# DressCode.net
KiCad netlist of a schematic drawn in EAGLE
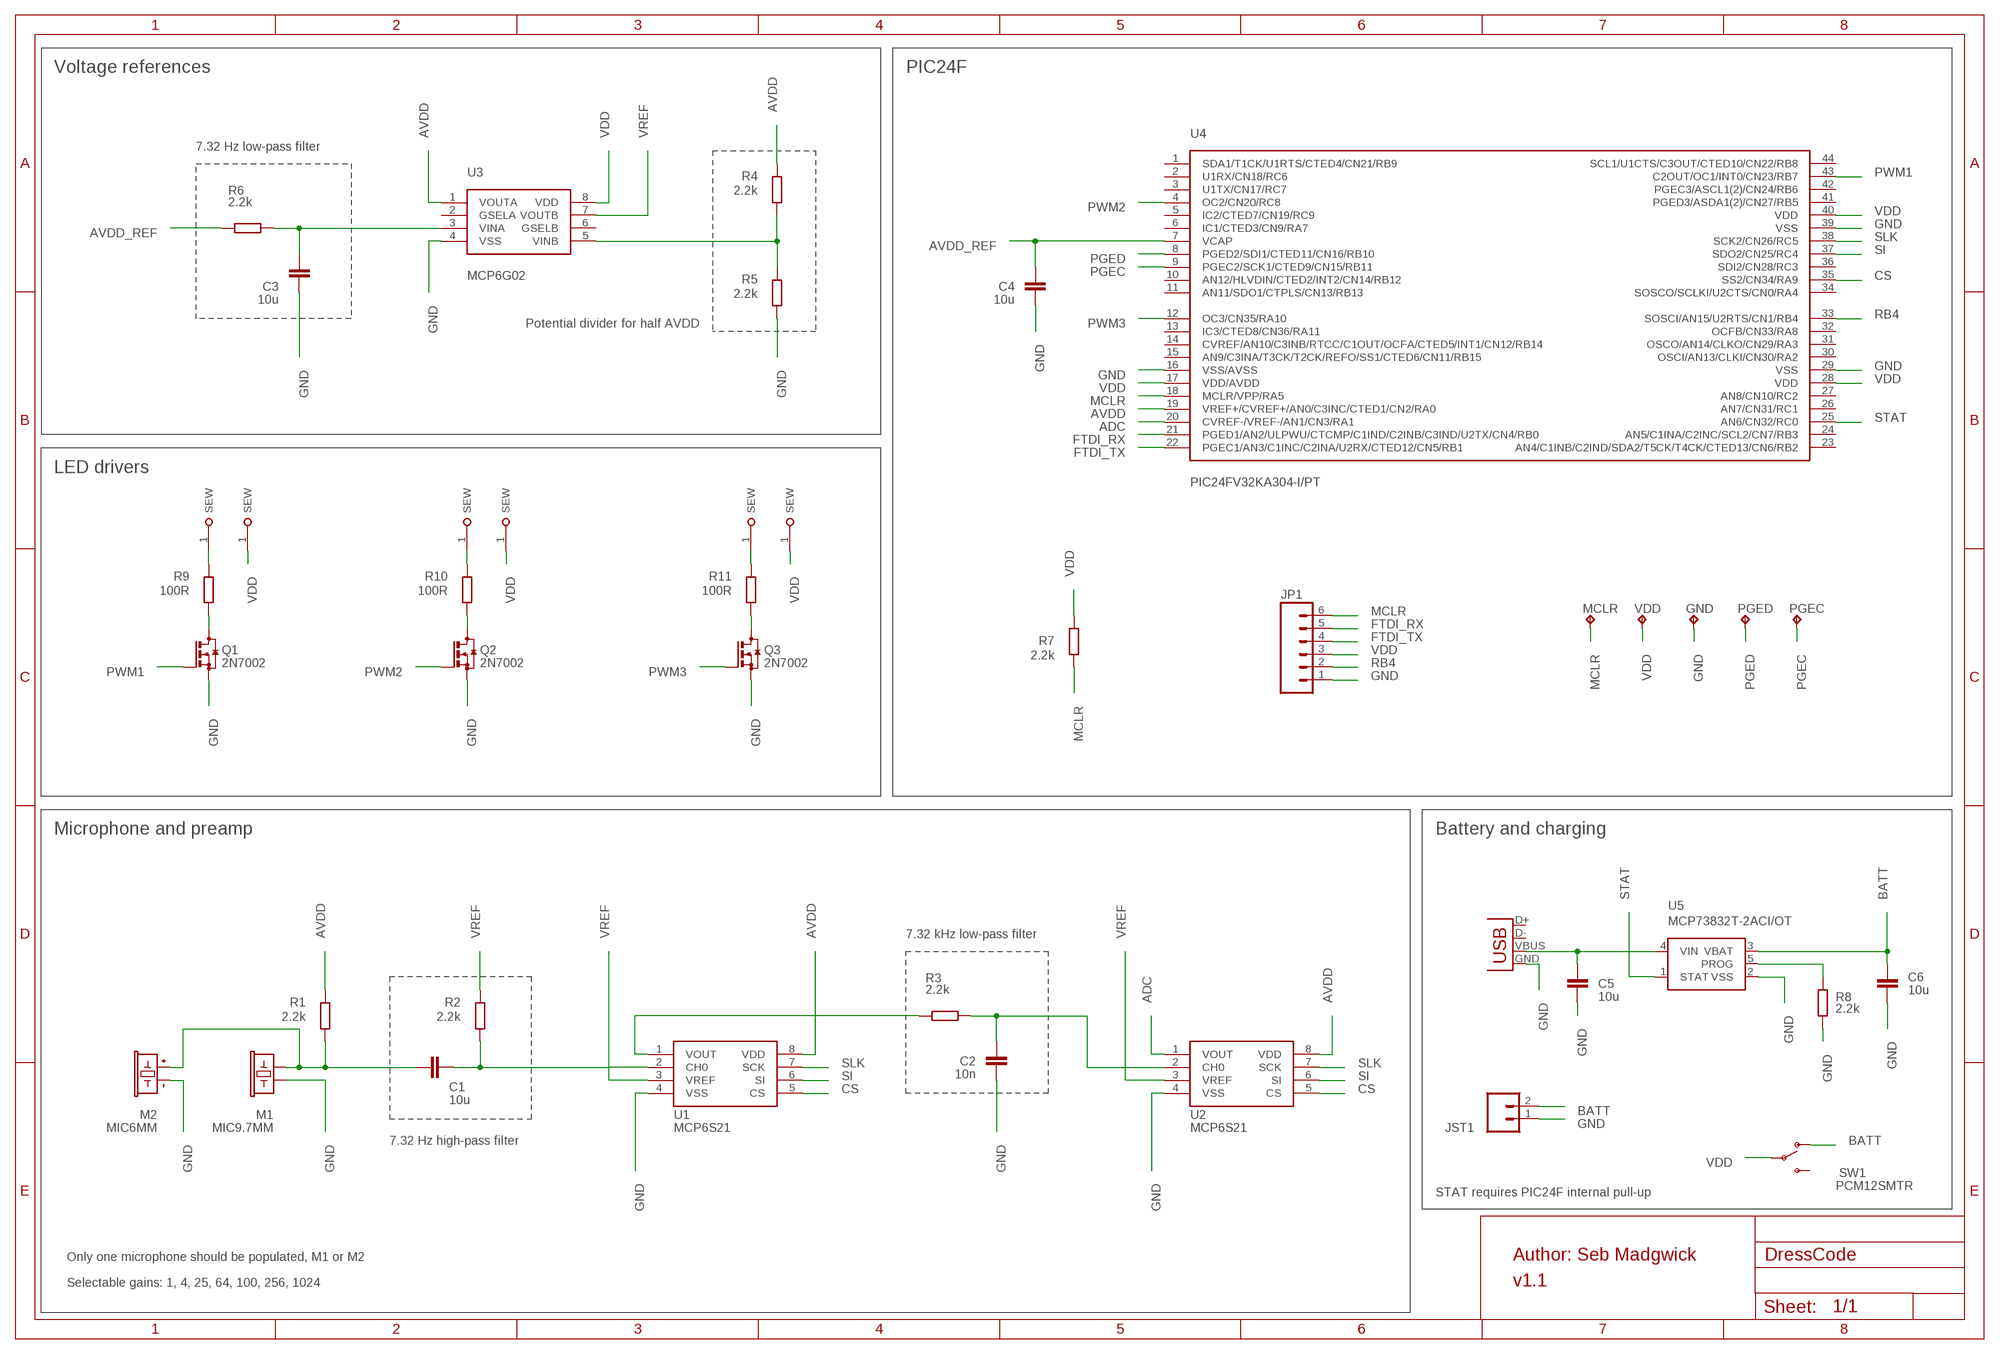
[diagram p0: schematic, sheet 1]

(export (version "E")
  (design (tool "Eeschema 10.0.6"))
  (components
    (comp (ref "C1")
      (value "10u")
      (footprint "eagle-import:C0805")
      (libsource (lib "eagle-import") (part "C-EUC0805"))
    )
    (comp (ref "C2")
      (value "10n")
      (footprint "eagle-import:C0805")
      (libsource (lib "eagle-import") (part "C-EUC0805"))
    )
    (comp (ref "C3")
      (value "10u")
      (footprint "eagle-import:C0805")
      (libsource (lib "eagle-import") (part "C-EUC0805"))
    )
    (comp (ref "C4")
      (value "10u")
      (footprint "eagle-import:C0805")
      (libsource (lib "eagle-import") (part "C-EUC0805"))
    )
    (comp (ref "C5")
      (value "10u")
      (footprint "eagle-import:C0805")
      (libsource (lib "eagle-import") (part "C-EUC0805"))
    )
    (comp (ref "C6")
      (value "10u")
      (footprint "eagle-import:C0805")
      (libsource (lib "eagle-import") (part "C-EUC0805"))
    )
    (comp (ref "GND")
      (value "TPTP16R")
      (footprint "eagle-import:TP16R")
      (libsource (lib "eagle-import") (part "TPTP16R"))
    )
    (comp (ref "JP1")
      (value "M06SIP")
      (footprint "eagle-import:1X06")
      (libsource (lib "eagle-import") (part "M06SIP"))
    )
    (comp (ref "JST1")
      (value "M02-JST-2MM-SMT")
      (footprint "eagle-import:JST-2-SMD")
      (libsource (lib "eagle-import") (part "M02-JST-2MM-SMT"))
    )
    (comp (ref "M1")
      (value "MIC9.7MM")
      (footprint "eagle-import:MIC-9.7MM")
      (libsource (lib "eagle-import") (part "MIC9.7MM"))
    )
    (comp (ref "M2")
      (value "MIC6MM")
      (footprint "eagle-import:MIC-SMD")
      (libsource (lib "eagle-import") (part "MIC6MM"))
    )
    (comp (ref "MCLR")
      (value "TPTP16R")
      (footprint "eagle-import:TP16R")
      (libsource (lib "eagle-import") (part "TPTP16R"))
    )
    (comp (ref "PGEC")
      (value "TPTP16R")
      (footprint "eagle-import:TP16R")
      (libsource (lib "eagle-import") (part "TPTP16R"))
    )
    (comp (ref "PGED")
      (value "TPTP16R")
      (footprint "eagle-import:TP16R")
      (libsource (lib "eagle-import") (part "TPTP16R"))
    )
    (comp (ref "Q1")
      (value "2N7002")
      (footprint "eagle-import:SOT23")
      (libsource (lib "eagle-import") (part "BSS123"))
    )
    (comp (ref "Q2")
      (value "2N7002")
      (footprint "eagle-import:SOT23")
      (libsource (lib "eagle-import") (part "BSS123"))
    )
    (comp (ref "Q3")
      (value "2N7002")
      (footprint "eagle-import:SOT23")
      (libsource (lib "eagle-import") (part "BSS123"))
    )
    (comp (ref "R1")
      (value "2.2k")
      (footprint "eagle-import:R0805")
      (libsource (lib "eagle-import") (part "R-EU_R0805"))
    )
    (comp (ref "R2")
      (value "2.2k")
      (footprint "eagle-import:R0805")
      (libsource (lib "eagle-import") (part "R-EU_R0805"))
    )
    (comp (ref "R3")
      (value "2.2k")
      (footprint "eagle-import:R0805")
      (libsource (lib "eagle-import") (part "R-EU_R0805"))
    )
    (comp (ref "R4")
      (value "2.2k")
      (footprint "eagle-import:R0805")
      (libsource (lib "eagle-import") (part "R-EU_R0805"))
    )
    (comp (ref "R5")
      (value "2.2k")
      (footprint "eagle-import:R0805")
      (libsource (lib "eagle-import") (part "R-EU_R0805"))
    )
    (comp (ref "R6")
      (value "2.2k")
      (footprint "eagle-import:R0805")
      (libsource (lib "eagle-import") (part "R-EU_R0805"))
    )
    (comp (ref "R7")
      (value "2.2k")
      (footprint "eagle-import:R0805")
      (libsource (lib "eagle-import") (part "R-EU_R0805"))
    )
    (comp (ref "R8")
      (value "2.2k")
      (footprint "eagle-import:R0805")
      (libsource (lib "eagle-import") (part "R-EU_R0805"))
    )
    (comp (ref "R9")
      (value "100R")
      (footprint "eagle-import:R0805")
      (libsource (lib "eagle-import") (part "R-EU_R0805"))
    )
    (comp (ref "R10")
      (value "100R")
      (footprint "eagle-import:R0805")
      (libsource (lib "eagle-import") (part "R-EU_R0805"))
    )
    (comp (ref "R11")
      (value "100R")
      (footprint "eagle-import:R0805")
      (libsource (lib "eagle-import") (part "R-EU_R0805"))
    )
    (comp (ref "SW1")
      (value "PCM12SMTR")
      (footprint "eagle-import:PCM12SMTR")
      (libsource (lib "eagle-import") (part "PCM12SMTR"))
    )
    (comp (ref "U$4")
      (value "DRESSCODE_SEW_PADC")
      (footprint "eagle-import:DRESSCODE_SEW_PAD_CIRC")
      (libsource (lib "eagle-import") (part "DRESSCODE_SEW_PADC"))
    )
    (comp (ref "U$5")
      (value "DRESSCODE_SEW_PADC")
      (footprint "eagle-import:DRESSCODE_SEW_PAD_CIRC")
      (libsource (lib "eagle-import") (part "DRESSCODE_SEW_PADC"))
    )
    (comp (ref "U$6")
      (value "DRESSCODE_SEW_PADC")
      (footprint "eagle-import:DRESSCODE_SEW_PAD_CIRC")
      (libsource (lib "eagle-import") (part "DRESSCODE_SEW_PADC"))
    )
    (comp (ref "U$7")
      (value "DRESSCODE_SEW_PADS")
      (footprint "eagle-import:DRESSCODE_SEW_PAD_SQR")
      (libsource (lib "eagle-import") (part "DRESSCODE_SEW_PADS"))
    )
    (comp (ref "U$8")
      (value "DRESSCODE_SEW_PADS")
      (footprint "eagle-import:DRESSCODE_SEW_PAD_SQR")
      (libsource (lib "eagle-import") (part "DRESSCODE_SEW_PADS"))
    )
    (comp (ref "U$10")
      (value "DRESSCODE_SEW_PADS")
      (footprint "eagle-import:DRESSCODE_SEW_PAD_SQR")
      (libsource (lib "eagle-import") (part "DRESSCODE_SEW_PADS"))
    )
    (comp (ref "U1")
      (value "MCP6S21")
      (footprint "eagle-import:SOIC-8")
      (libsource (lib "eagle-import") (part "MCP6S21"))
    )
    (comp (ref "U2")
      (value "MCP6S21")
      (footprint "eagle-import:SOIC-8")
      (libsource (lib "eagle-import") (part "MCP6S21"))
    )
    (comp (ref "U3")
      (value "MCP6G02")
      (footprint "eagle-import:SOIC-8")
      (libsource (lib "eagle-import") (part "MCP6G02"))
    )
    (comp (ref "U4")
      (value "PIC24FV32KA304-I/PT")
      (footprint "eagle-import:TQFP44")
      (libsource (lib "eagle-import") (part "PIC24FV32KA304-I/PT"))
    )
    (comp (ref "U5")
      (value "MCP73832T-2ACI/OT")
      (footprint "eagle-import:SOT23-5")
      (libsource (lib "eagle-import") (part "MCP73831"))
    )
    (comp (ref "USB1")
      (value "USB-MICROB")
      (footprint "eagle-import:USB-MICROB")
      (libsource (lib "eagle-import") (part "USB-MICROB"))
    )
    (comp (ref "VDD")
      (value "TPTP16R")
      (footprint "eagle-import:TP16R")
      (libsource (lib "eagle-import") (part "TPTP16R"))
    )
  )
  (nets
    (net (code "1") (name "/ADC") (class "Default")
      (node (ref "U2") (pin "1") (pinfunction "VOUT_1") (pintype "bidirectional"))
      (node (ref "U4") (pin "20") (pinfunction "CVREF-/VREF-/AN1/CN3/RA1_20") (pintype "bidirectional"))
    )
    (net (code "2") (name "/AVDD") (class "Default")
      (node (ref "R1") (pin "2") (pinfunction "2_2") (pintype "passive"))
      (node (ref "R4") (pin "2") (pinfunction "2_2") (pintype "passive"))
      (node (ref "U1") (pin "8") (pinfunction "VDD_8") (pintype "bidirectional"))
      (node (ref "U2") (pin "8") (pinfunction "VDD_8") (pintype "bidirectional"))
      (node (ref "U3") (pin "1") (pinfunction "VOUTA_1") (pintype "bidirectional"))
      (node (ref "U4") (pin "19") (pinfunction "VREF+/CVREF+/AN0/C3INC/CTED1/CN2/RA0_19") (pintype "bidirectional"))
    )
    (net (code "3") (name "/AVDD_REF") (class "Default")
      (node (ref "C4") (pin "2") (pinfunction "2_2") (pintype "passive"))
      (node (ref "R6") (pin "1") (pinfunction "1_1") (pintype "passive"))
      (node (ref "U4") (pin "7") (pinfunction "VCAP_7") (pintype "bidirectional"))
    )
    (net (code "4") (name "/BATT") (class "Default")
      (node (ref "C6") (pin "2") (pinfunction "2_2") (pintype "passive"))
      (node (ref "JST1") (pin "2") (pinfunction "2_2") (pintype "passive"))
      (node (ref "SW1") (pin "1") (pinfunction "O_1") (pintype "passive"))
      (node (ref "U5") (pin "3") (pinfunction "VBAT_3") (pintype "power_in"))
    )
    (net (code "5") (name "/CS") (class "Default")
      (node (ref "U1") (pin "5") (pinfunction "CS_5") (pintype "bidirectional"))
      (node (ref "U2") (pin "5") (pinfunction "CS_5") (pintype "bidirectional"))
      (node (ref "U4") (pin "35") (pinfunction "SS2/CN34/RA9_35") (pintype "bidirectional"))
    )
    (net (code "6") (name "/FTDI_RX") (class "Default")
      (node (ref "JP1") (pin "5") (pinfunction "5_5") (pintype "passive"))
      (node (ref "U4") (pin "21") (pinfunction "PGED1/AN2/ULPWU/CTCMP/C1IND/C2INB/C3IND/U2TX/CN4/RB0_21") (pintype "bidirectional"))
    )
    (net (code "7") (name "/FTDI_TX") (class "Default")
      (node (ref "JP1") (pin "4") (pinfunction "4_4") (pintype "passive"))
      (node (ref "U4") (pin "22") (pinfunction "PGEC1/AN3/C1INC/C2INA/U2RX/CTED12/CN5/RB1_22") (pintype "bidirectional"))
    )
    (net (code "8") (name "/GND") (class "Default")
      (node (ref "C2") (pin "2") (pinfunction "2_2") (pintype "passive"))
      (node (ref "C3") (pin "1") (pinfunction "1_1") (pintype "passive"))
      (node (ref "C4") (pin "1") (pinfunction "1_1") (pintype "passive"))
      (node (ref "C5") (pin "1") (pinfunction "1_1") (pintype "passive"))
      (node (ref "C6") (pin "1") (pinfunction "1_1") (pintype "passive"))
      (node (ref "GND") (pin "TP") (pinfunction "TP_TP") (pintype "input"))
      (node (ref "JP1") (pin "1") (pinfunction "1_1") (pintype "passive"))
      (node (ref "JST1") (pin "1") (pinfunction "1_1") (pintype "passive"))
      (node (ref "M1") (pin "2") (pinfunction "2_2") (pintype "passive"))
      (node (ref "M2") (pin "-") (pinfunction "-_-") (pintype "passive"))
      (node (ref "Q1") (pin "2") (pinfunction "S_2") (pintype "passive"))
      (node (ref "Q2") (pin "2") (pinfunction "S_2") (pintype "passive"))
      (node (ref "Q3") (pin "2") (pinfunction "S_2") (pintype "passive"))
      (node (ref "R5") (pin "1") (pinfunction "1_1") (pintype "passive"))
      (node (ref "R8") (pin "1") (pinfunction "1_1") (pintype "passive"))
      (node (ref "U1") (pin "4") (pinfunction "VSS_4") (pintype "bidirectional"))
      (node (ref "U2") (pin "4") (pinfunction "VSS_4") (pintype "bidirectional"))
      (node (ref "U3") (pin "4") (pinfunction "VSS_4") (pintype "bidirectional"))
      (node (ref "U4") (pin "16") (pinfunction "VSS/AVSS_16") (pintype "bidirectional"))
      (node (ref "U4") (pin "29") (pinfunction "VSS_29") (pintype "bidirectional"))
      (node (ref "U4") (pin "39") (pinfunction "VSS_39") (pintype "bidirectional"))
      (node (ref "U5") (pin "2") (pinfunction "VSS_2") (pintype "power_in"))
      (node (ref "USB1") (pin "GND") (pinfunction "GND_GND") (pintype "bidirectional"))
    )
    (net (code "9") (name "/MCLR") (class "Default")
      (node (ref "JP1") (pin "6") (pinfunction "6_6") (pintype "passive"))
      (node (ref "MCLR") (pin "TP") (pinfunction "TP_TP") (pintype "input"))
      (node (ref "R7") (pin "1") (pinfunction "1_1") (pintype "passive"))
      (node (ref "U4") (pin "18") (pinfunction "MCLR/VPP/RA5_18") (pintype "bidirectional"))
    )
    (net (code "10") (name "/PGEC") (class "Default")
      (node (ref "PGEC") (pin "TP") (pinfunction "TP_TP") (pintype "input"))
      (node (ref "U4") (pin "9") (pinfunction "PGEC2/SCK1/CTED9/CN15/RB11_9") (pintype "bidirectional"))
    )
    (net (code "11") (name "/PGED") (class "Default")
      (node (ref "PGED") (pin "TP") (pinfunction "TP_TP") (pintype "input"))
      (node (ref "U4") (pin "8") (pinfunction "PGED2/SDI1/CTED11/CN16/RB10_8") (pintype "bidirectional"))
    )
    (net (code "12") (name "/PWM1") (class "Default")
      (node (ref "Q1") (pin "1") (pinfunction "G_1") (pintype "passive"))
      (node (ref "U4") (pin "43") (pinfunction "C2OUT/OC1/INT0/CN23/RB7_43") (pintype "bidirectional"))
    )
    (net (code "13") (name "/PWM2") (class "Default")
      (node (ref "Q2") (pin "1") (pinfunction "G_1") (pintype "passive"))
      (node (ref "U4") (pin "4") (pinfunction "OC2/CN20/RC8_4") (pintype "bidirectional"))
    )
    (net (code "14") (name "/PWM3") (class "Default")
      (node (ref "Q3") (pin "1") (pinfunction "G_1") (pintype "passive"))
      (node (ref "U4") (pin "12") (pinfunction "OC3/CN35/RA10_12") (pintype "bidirectional"))
    )
    (net (code "15") (name "/RB4") (class "Default")
      (node (ref "JP1") (pin "2") (pinfunction "2_2") (pintype "passive"))
      (node (ref "U4") (pin "33") (pinfunction "SOSCI/AN15/U2RTS/CN1/RB4_33") (pintype "bidirectional"))
    )
    (net (code "16") (name "/SI") (class "Default")
      (node (ref "U1") (pin "6") (pinfunction "SI_6") (pintype "bidirectional"))
      (node (ref "U2") (pin "6") (pinfunction "SI_6") (pintype "bidirectional"))
      (node (ref "U4") (pin "37") (pinfunction "SDO2/CN25/RC4_37") (pintype "bidirectional"))
    )
    (net (code "17") (name "/SLK") (class "Default")
      (node (ref "U1") (pin "7") (pinfunction "SCK_7") (pintype "bidirectional"))
      (node (ref "U2") (pin "7") (pinfunction "SCK_7") (pintype "bidirectional"))
      (node (ref "U4") (pin "38") (pinfunction "SCK2/CN26/RC5_38") (pintype "bidirectional"))
    )
    (net (code "18") (name "/STAT") (class "Default")
      (node (ref "U4") (pin "25") (pinfunction "AN6/CN32/RC0_25") (pintype "bidirectional"))
      (node (ref "U5") (pin "1") (pinfunction "STAT_1") (pintype "output"))
    )
    (net (code "19") (name "/VDD") (class "Default")
      (node (ref "JP1") (pin "3") (pinfunction "3_3") (pintype "passive"))
      (node (ref "R7") (pin "2") (pinfunction "2_2") (pintype "passive"))
      (node (ref "SW1") (pin "2") (pinfunction "P_2") (pintype "passive"))
      (node (ref "U$4") (pin "1") (pinfunction "SEW_1") (pintype "bidirectional"))
      (node (ref "U$5") (pin "1") (pinfunction "SEW_1") (pintype "bidirectional"))
      (node (ref "U$6") (pin "1") (pinfunction "SEW_1") (pintype "bidirectional"))
      (node (ref "U3") (pin "8") (pinfunction "VDD_8") (pintype "bidirectional"))
      (node (ref "U4") (pin "17") (pinfunction "VDD/AVDD_17") (pintype "bidirectional"))
      (node (ref "U4") (pin "28") (pinfunction "VDD_28") (pintype "bidirectional"))
      (node (ref "U4") (pin "40") (pinfunction "VDD_40") (pintype "bidirectional"))
      (node (ref "VDD") (pin "TP") (pinfunction "TP_TP") (pintype "input"))
    )
    (net (code "20") (name "/VREF") (class "Default")
      (node (ref "R2") (pin "2") (pinfunction "2_2") (pintype "passive"))
      (node (ref "U1") (pin "3") (pinfunction "VREF_3") (pintype "bidirectional"))
      (node (ref "U2") (pin "3") (pinfunction "VREF_3") (pintype "bidirectional"))
      (node (ref "U3") (pin "7") (pinfunction "VOUTB_7") (pintype "bidirectional"))
    )
    (net (code "21") (name "Net-(C1-Pad1)") (class "Default")
      (node (ref "C1") (pin "1") (pinfunction "1_1") (pintype "passive"))
      (node (ref "M1") (pin "1") (pinfunction "1_1") (pintype "passive"))
      (node (ref "M2") (pin "+") (pinfunction "+_+") (pintype "passive"))
      (node (ref "R1") (pin "1") (pinfunction "1_1") (pintype "passive"))
    )
    (net (code "22") (name "Net-(Q1-D)") (class "Default")
      (node (ref "Q1") (pin "3") (pinfunction "D_3") (pintype "passive"))
      (node (ref "R9") (pin "1") (pinfunction "1_1") (pintype "passive"))
    )
    (net (code "23") (name "Net-(Q2-D)") (class "Default")
      (node (ref "Q2") (pin "3") (pinfunction "D_3") (pintype "passive"))
      (node (ref "R10") (pin "1") (pinfunction "1_1") (pintype "passive"))
    )
    (net (code "24") (name "Net-(Q3-D)") (class "Default")
      (node (ref "Q3") (pin "3") (pinfunction "D_3") (pintype "passive"))
      (node (ref "R11") (pin "1") (pinfunction "1_1") (pintype "passive"))
    )
    (net (code "25") (name "Net-(U$7-SEW)") (class "Default")
      (node (ref "R9") (pin "2") (pinfunction "2_2") (pintype "passive"))
      (node (ref "U$7") (pin "1") (pinfunction "SEW_1") (pintype "bidirectional"))
    )
    (net (code "26") (name "Net-(U$8-SEW)") (class "Default")
      (node (ref "R10") (pin "2") (pinfunction "2_2") (pintype "passive"))
      (node (ref "U$8") (pin "1") (pinfunction "SEW_1") (pintype "bidirectional"))
    )
    (net (code "27") (name "Net-(U$10-SEW)") (class "Default")
      (node (ref "R11") (pin "2") (pinfunction "2_2") (pintype "passive"))
      (node (ref "U$10") (pin "1") (pinfunction "SEW_1") (pintype "bidirectional"))
    )
    (net (code "28") (name "Net-(U1-CH0)") (class "Default")
      (node (ref "C1") (pin "2") (pinfunction "2_2") (pintype "passive"))
      (node (ref "R2") (pin "1") (pinfunction "1_1") (pintype "passive"))
      (node (ref "U1") (pin "2") (pinfunction "CH0_2") (pintype "bidirectional"))
    )
    (net (code "29") (name "Net-(U1-VOUT)") (class "Default")
      (node (ref "R3") (pin "1") (pinfunction "1_1") (pintype "passive"))
      (node (ref "U1") (pin "1") (pinfunction "VOUT_1") (pintype "bidirectional"))
    )
    (net (code "30") (name "Net-(U2-CH0)") (class "Default")
      (node (ref "C2") (pin "1") (pinfunction "1_1") (pintype "passive"))
      (node (ref "R3") (pin "2") (pinfunction "2_2") (pintype "passive"))
      (node (ref "U2") (pin "2") (pinfunction "CH0_2") (pintype "bidirectional"))
    )
    (net (code "31") (name "Net-(U3-VINA)") (class "Default")
      (node (ref "C3") (pin "2") (pinfunction "2_2") (pintype "passive"))
      (node (ref "R6") (pin "2") (pinfunction "2_2") (pintype "passive"))
      (node (ref "U3") (pin "3") (pinfunction "VINA_3") (pintype "bidirectional"))
    )
    (net (code "32") (name "Net-(U3-VINB)") (class "Default")
      (node (ref "R4") (pin "1") (pinfunction "1_1") (pintype "passive"))
      (node (ref "R5") (pin "2") (pinfunction "2_2") (pintype "passive"))
      (node (ref "U3") (pin "5") (pinfunction "VINB_5") (pintype "bidirectional"))
    )
    (net (code "33") (name "Net-(U5-PROG)") (class "Default")
      (node (ref "R8") (pin "2") (pinfunction "2_2") (pintype "passive"))
      (node (ref "U5") (pin "5") (pinfunction "PROG_5") (pintype "input"))
    )
    (net (code "34") (name "Net-(U5-VIN)") (class "Default")
      (node (ref "C5") (pin "2") (pinfunction "2_2") (pintype "passive"))
      (node (ref "U5") (pin "4") (pinfunction "VIN_4") (pintype "power_in"))
      (node (ref "USB1") (pin "VBUS") (pinfunction "VBUS_VBUS") (pintype "bidirectional"))
    )
    (net (code "35") (name "unconnected-(SW1-S-Pad3)") (class "Default")
      (node (ref "SW1") (pin "3") (pinfunction "S_3") (pintype "passive"))
    )
    (net (code "36") (name "unconnected-(U3-GSELA-Pad2)") (class "Default")
      (node (ref "U3") (pin "2") (pinfunction "GSELA_2") (pintype "bidirectional"))
    )
    (net (code "37") (name "unconnected-(U3-GSELB-Pad6)") (class "Default")
      (node (ref "U3") (pin "6") (pinfunction "GSELB_6") (pintype "bidirectional"))
    )
    (net (code "38") (name "unconnected-(U4-AN4{slash}C1INB{slash}C2IND{slash}SDA2{slash}T5CK{slash}T4CK{slash}CTED13{slash}CN6{slash}RB2-Pad23)") (class "Default")
      (node (ref "U4") (pin "23") (pinfunction "AN4/C1INB/C2IND/SDA2/T5CK/T4CK/CTED13/CN6/RB2_23") (pintype "bidirectional"))
    )
    (net (code "39") (name "unconnected-(U4-AN5{slash}C1INA{slash}C2INC{slash}SCL2{slash}CN7{slash}RB3-Pad24)") (class "Default")
      (node (ref "U4") (pin "24") (pinfunction "AN5/C1INA/C2INC/SCL2/CN7/RB3_24") (pintype "bidirectional"))
    )
    (net (code "40") (name "unconnected-(U4-AN7{slash}CN31{slash}RC1-Pad26)") (class "Default")
      (node (ref "U4") (pin "26") (pinfunction "AN7/CN31/RC1_26") (pintype "bidirectional"))
    )
    (net (code "41") (name "unconnected-(U4-AN8{slash}CN10{slash}RC2-Pad27)") (class "Default")
      (node (ref "U4") (pin "27") (pinfunction "AN8/CN10/RC2_27") (pintype "bidirectional"))
    )
    (net (code "42") (name "unconnected-(U4-AN9{slash}C3INA{slash}T3CK{slash}T2CK{slash}REFO{slash}SS1{slash}CTED6{slash}CN11{slash}RB15-Pad15)") (class "Default")
      (node (ref "U4") (pin "15") (pinfunction "AN9/C3INA/T3CK/T2CK/REFO/SS1/CTED6/CN11/RB15_15") (pintype "bidirectional"))
    )
    (net (code "43") (name "unconnected-(U4-AN11{slash}SDO1{slash}CTPLS{slash}CN13{slash}RB13-Pad11)") (class "Default")
      (node (ref "U4") (pin "11") (pinfunction "AN11/SDO1/CTPLS/CN13/RB13_11") (pintype "bidirectional"))
    )
    (net (code "44") (name "unconnected-(U4-AN12{slash}HLVDIN{slash}CTED2{slash}INT2{slash}CN14{slash}RB12-Pad10)") (class "Default")
      (node (ref "U4") (pin "10") (pinfunction "AN12/HLVDIN/CTED2/INT2/CN14/RB12_10") (pintype "bidirectional"))
    )
    (net (code "45") (name "unconnected-(U4-CVREF{slash}AN10{slash}C3INB{slash}RTCC{slash}C1OUT{slash}OCFA{slash}CTED5{slash}INT1{slash}CN12{slash}RB14-Pad14)") (class "Default")
      (node (ref "U4") (pin "14") (pinfunction "CVREF/AN10/C3INB/RTCC/C1OUT/OCFA/CTED5/INT1/CN12/RB14_14") (pintype "bidirectional"))
    )
    (net (code "46") (name "unconnected-(U4-IC1{slash}CTED3{slash}CN9{slash}RA7-Pad6)") (class "Default")
      (node (ref "U4") (pin "6") (pinfunction "IC1/CTED3/CN9/RA7_6") (pintype "bidirectional"))
    )
    (net (code "47") (name "unconnected-(U4-IC2{slash}CTED7{slash}CN19{slash}RC9-Pad5)") (class "Default")
      (node (ref "U4") (pin "5") (pinfunction "IC2/CTED7/CN19/RC9_5") (pintype "bidirectional"))
    )
    (net (code "48") (name "unconnected-(U4-IC3{slash}CTED8{slash}CN36{slash}RA11-Pad13)") (class "Default")
      (node (ref "U4") (pin "13") (pinfunction "IC3/CTED8/CN36/RA11_13") (pintype "bidirectional"))
    )
    (net (code "49") (name "unconnected-(U4-OCFB{slash}CN33{slash}RA8-Pad32)") (class "Default")
      (node (ref "U4") (pin "32") (pinfunction "OCFB/CN33/RA8_32") (pintype "bidirectional"))
    )
    (net (code "50") (name "unconnected-(U4-OSCI{slash}AN13{slash}CLKI{slash}CN30{slash}RA2-Pad30)") (class "Default")
      (node (ref "U4") (pin "30") (pinfunction "OSCI/AN13/CLKI/CN30/RA2_30") (pintype "bidirectional"))
    )
    (net (code "51") (name "unconnected-(U4-OSCO{slash}AN14{slash}CLKO{slash}CN29{slash}RA3-Pad31)") (class "Default")
      (node (ref "U4") (pin "31") (pinfunction "OSCO/AN14/CLKO/CN29/RA3_31") (pintype "bidirectional"))
    )
    (net (code "52") (name "unconnected-(U4-PGEC3{slash}ASCL1(2){slash}CN24{slash}RB6-Pad42)") (class "Default")
      (node (ref "U4") (pin "42") (pinfunction "PGEC3/ASCL1(2)/CN24/RB6_42") (pintype "bidirectional"))
    )
    (net (code "53") (name "unconnected-(U4-PGED3{slash}ASDA1(2){slash}CN27{slash}RB5-Pad41)") (class "Default")
      (node (ref "U4") (pin "41") (pinfunction "PGED3/ASDA1(2)/CN27/RB5_41") (pintype "bidirectional"))
    )
    (net (code "54") (name "unconnected-(U4-SCL1{slash}U1CTS{slash}C3OUT{slash}CTED10{slash}CN22{slash}RB8-Pad44)") (class "Default")
      (node (ref "U4") (pin "44") (pinfunction "SCL1/U1CTS/C3OUT/CTED10/CN22/RB8_44") (pintype "bidirectional"))
    )
    (net (code "55") (name "unconnected-(U4-SDA1{slash}T1CK{slash}U1RTS{slash}CTED4{slash}CN21{slash}RB9-Pad1)") (class "Default")
      (node (ref "U4") (pin "1") (pinfunction "SDA1/T1CK/U1RTS/CTED4/CN21/RB9_1") (pintype "bidirectional"))
    )
    (net (code "56") (name "unconnected-(U4-SDI2{slash}CN28{slash}RC3-Pad36)") (class "Default")
      (node (ref "U4") (pin "36") (pinfunction "SDI2/CN28/RC3_36") (pintype "bidirectional"))
    )
    (net (code "57") (name "unconnected-(U4-SOSCO{slash}SCLKI{slash}U2CTS{slash}CN0{slash}RA4-Pad34)") (class "Default")
      (node (ref "U4") (pin "34") (pinfunction "SOSCO/SCLKI/U2CTS/CN0/RA4_34") (pintype "bidirectional"))
    )
    (net (code "58") (name "unconnected-(U4-U1RX{slash}CN18{slash}RC6-Pad2)") (class "Default")
      (node (ref "U4") (pin "2") (pinfunction "U1RX/CN18/RC6_2") (pintype "bidirectional"))
    )
    (net (code "59") (name "unconnected-(U4-U1TX{slash}CN17{slash}RC7-Pad3)") (class "Default")
      (node (ref "U4") (pin "3") (pinfunction "U1TX/CN17/RC7_3") (pintype "bidirectional"))
    )
    (net (code "60") (name "unconnected-(USB1-PadD+)") (class "Default")
      (node (ref "USB1") (pin "D+") (pinfunction "D+_D+") (pintype "bidirectional"))
    )
    (net (code "61") (name "unconnected-(USB1-PadD-)") (class "Default")
      (node (ref "USB1") (pin "D-") (pinfunction "D-_D-") (pintype "bidirectional"))
    )
  )
)
